# pas_ant.net
KiCad netlist of a schematic drawn in EAGLE
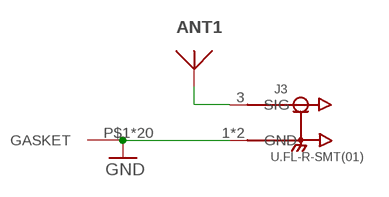
[diagram p0: schematic, sheet 1]

(export (version "E")
  (design (tool "Eeschema 10.0.6"))
  (components
    (comp (ref "ANT1")
      (value "ANT1590-2540A")
      (footprint "eagle-import:2540A")
      (libsource (lib "eagle-import") (part "ANT1590-2540A"))
    )
    (comp (ref "J3")
      (value "U.FL-R-SMT(01)")
      (footprint "eagle-import:HRS_U.FL-R-SMT(01)")
      (fields (field (name "MF") "Hirose") (field (name "MP") "U.FL-R-SMT_01_"))
      (libsource (lib "eagle-import") (part "U.FL-R-SMT(01)"))
    )
    (comp (ref "U$1")
      (value "2118718-2")
      (footprint "eagle-import:2118717-2")
      (libsource (lib "eagle-import") (part "2118718-2"))
    )
  )
  (nets
    (net (code "1") (name "GND") (class "Default")
      (node (ref "J3") (pin "1") (pinfunction "GND_1") (pintype "passive"))
      (node (ref "J3") (pin "2") (pinfunction "GND_2") (pintype "passive"))
      (node (ref "U$1") (pin "P$1") (pinfunction "GASKET_P$1") (pintype "bidirectional"))
      (node (ref "U$1") (pin "P$10") (pinfunction "GASKET_P$10") (pintype "bidirectional"))
      (node (ref "U$1") (pin "P$11") (pinfunction "GASKET_P$11") (pintype "bidirectional"))
      (node (ref "U$1") (pin "P$12") (pinfunction "GASKET_P$12") (pintype "bidirectional"))
      (node (ref "U$1") (pin "P$13") (pinfunction "GASKET_P$13") (pintype "bidirectional"))
      (node (ref "U$1") (pin "P$14") (pinfunction "GASKET_P$14") (pintype "bidirectional"))
      (node (ref "U$1") (pin "P$15") (pinfunction "GASKET_P$15") (pintype "bidirectional"))
      (node (ref "U$1") (pin "P$16") (pinfunction "GASKET_P$16") (pintype "bidirectional"))
      (node (ref "U$1") (pin "P$17") (pinfunction "GASKET_P$17") (pintype "bidirectional"))
      (node (ref "U$1") (pin "P$18") (pinfunction "GASKET_P$18") (pintype "bidirectional"))
      (node (ref "U$1") (pin "P$19") (pinfunction "GASKET_P$19") (pintype "bidirectional"))
      (node (ref "U$1") (pin "P$2") (pinfunction "GASKET_P$2") (pintype "bidirectional"))
      (node (ref "U$1") (pin "P$20") (pinfunction "GASKET_P$20") (pintype "bidirectional"))
      (node (ref "U$1") (pin "P$3") (pinfunction "GASKET_P$3") (pintype "bidirectional"))
      (node (ref "U$1") (pin "P$4") (pinfunction "GASKET_P$4") (pintype "bidirectional"))
      (node (ref "U$1") (pin "P$5") (pinfunction "GASKET_P$5") (pintype "bidirectional"))
      (node (ref "U$1") (pin "P$6") (pinfunction "GASKET_P$6") (pintype "bidirectional"))
      (node (ref "U$1") (pin "P$7") (pinfunction "GASKET_P$7") (pintype "bidirectional"))
      (node (ref "U$1") (pin "P$8") (pinfunction "GASKET_P$8") (pintype "bidirectional"))
      (node (ref "U$1") (pin "P$9") (pinfunction "GASKET_P$9") (pintype "bidirectional"))
    )
    (net (code "2") (name "Net-(J3-SIG)") (class "Default")
      (node (ref "ANT1") (pin "P$1") (pinfunction "P$1_P$1") (pintype "bidirectional"))
      (node (ref "J3") (pin "3") (pinfunction "SIG_3") (pintype "passive"))
    )
  )
)
